# solar_datalogger_workshop.net
KiCad netlist of a schematic drawn in EAGLE
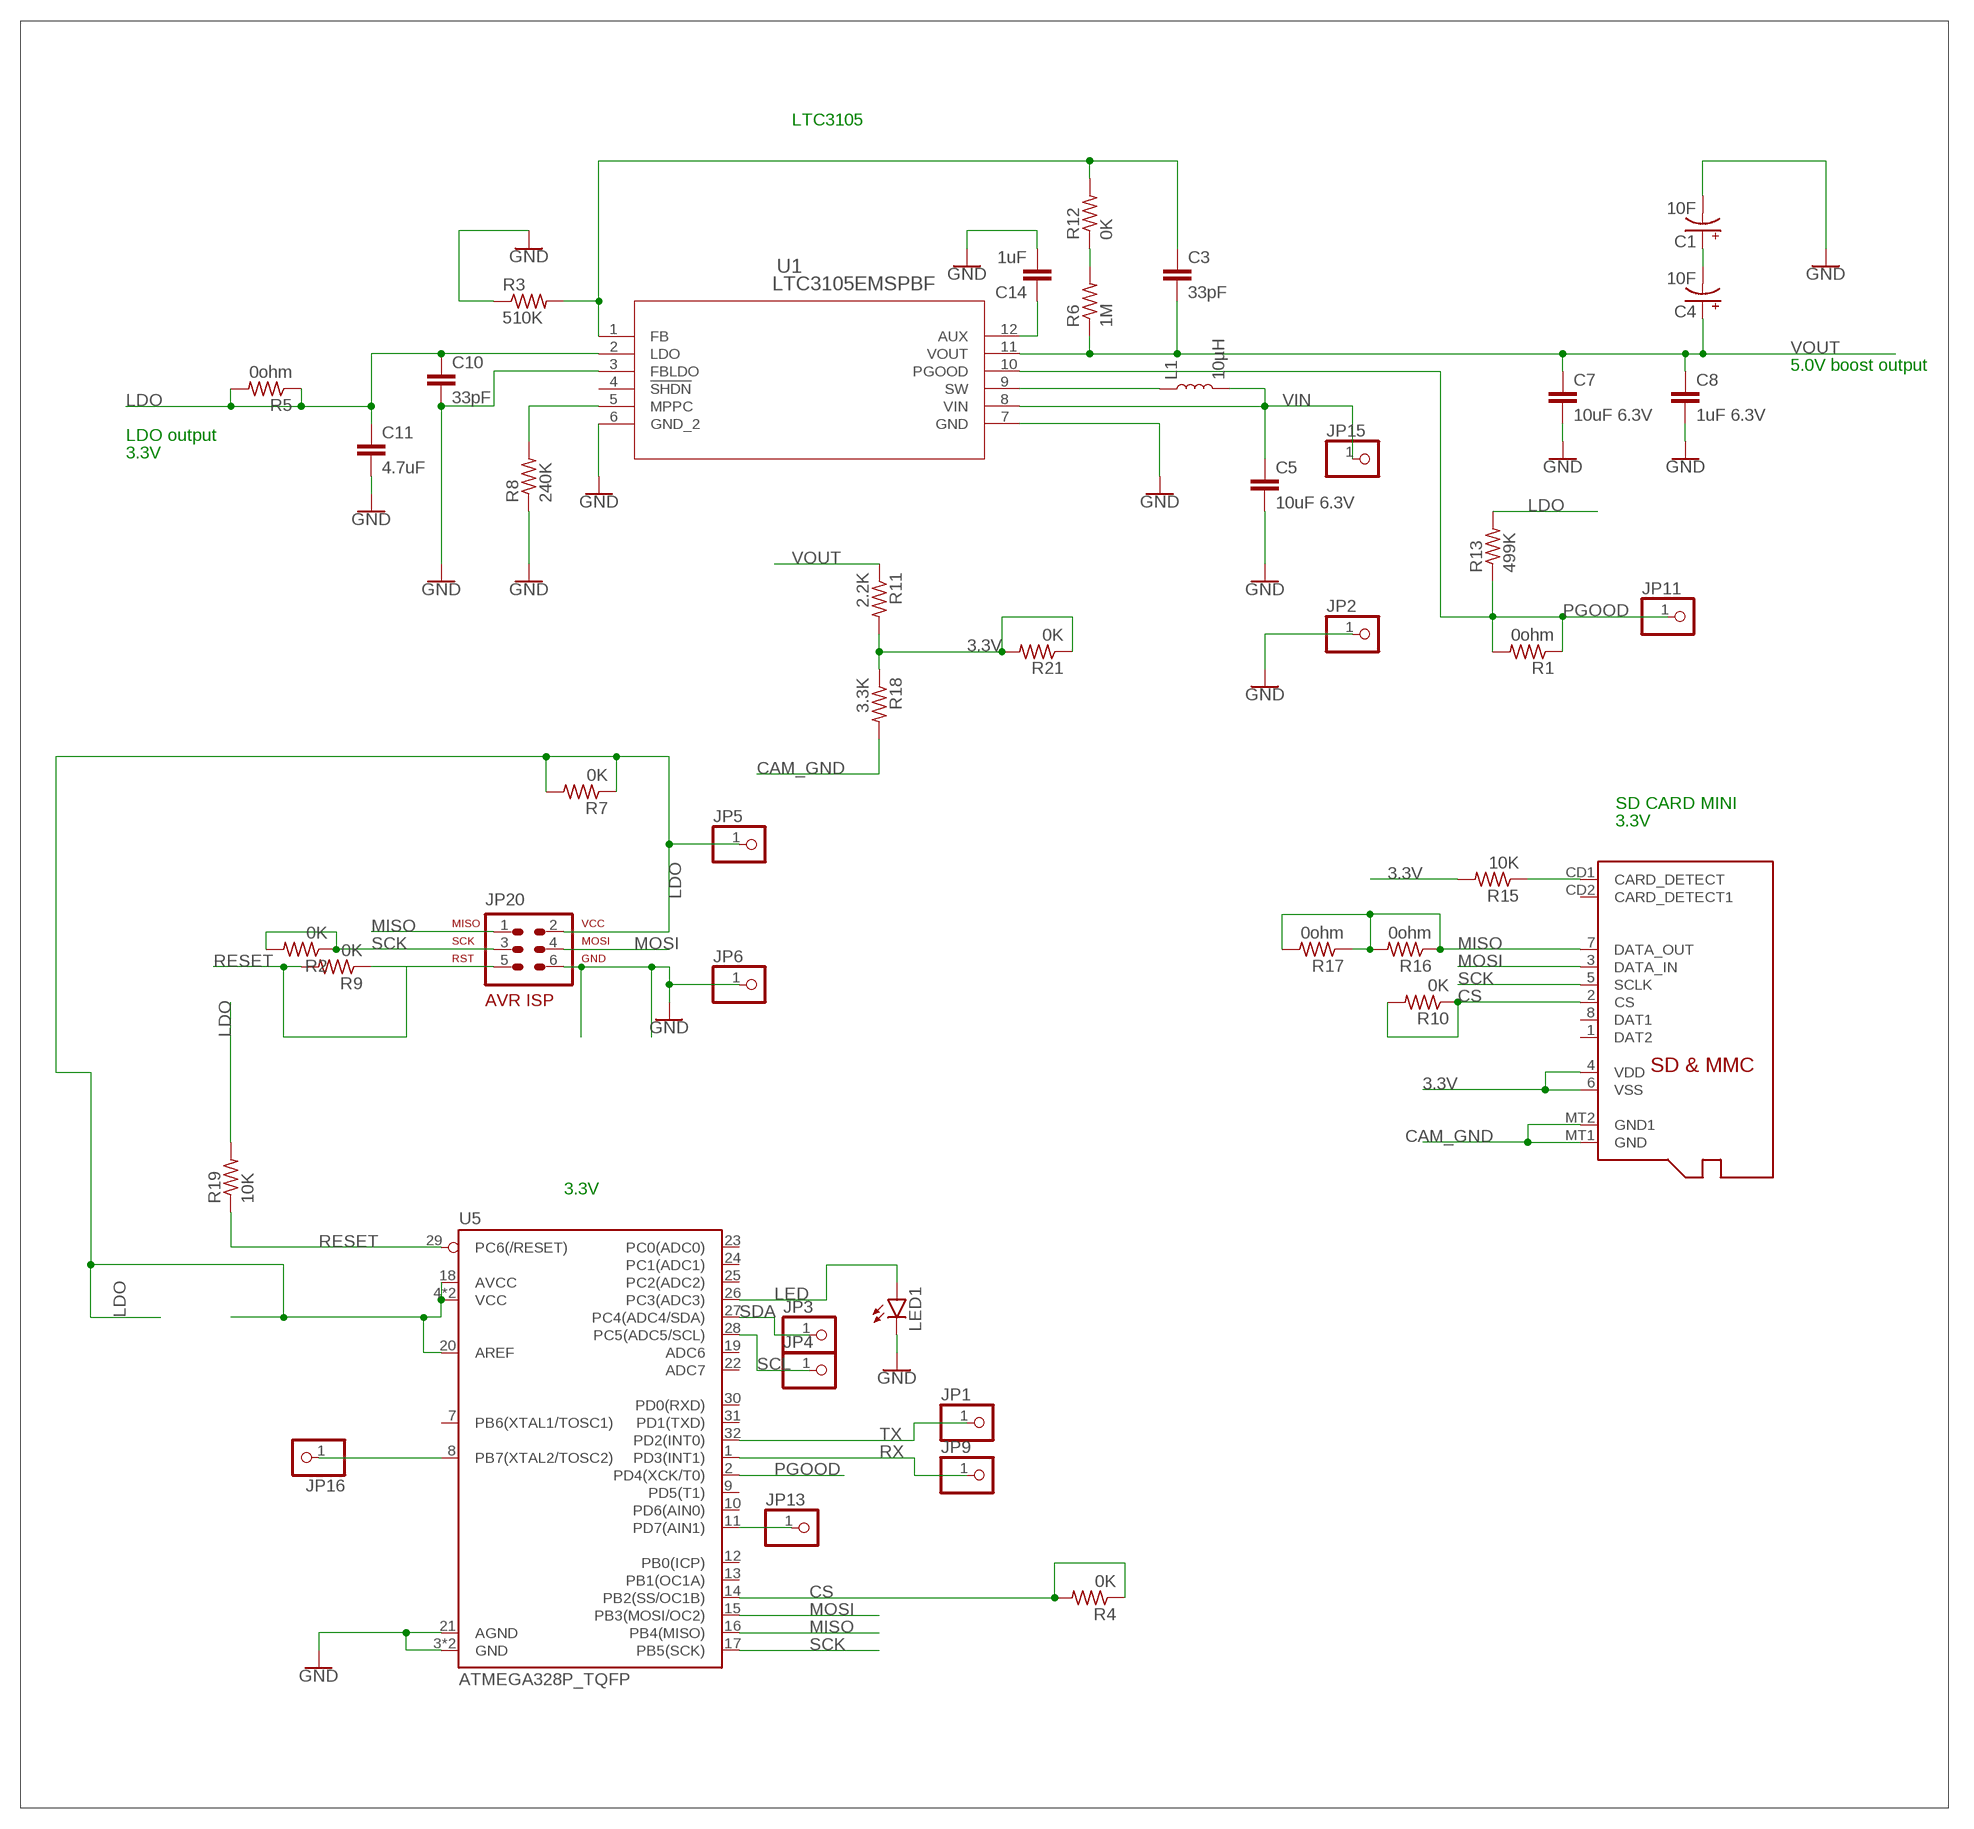
[diagram p0: schematic, sheet 1]

(export (version "E")
  (design (tool "Eeschema 10.0.6"))
  (components
    (comp (ref "C1")
      (value "10F")
      (footprint "eagle-import:CAP-RADIAL-5MM-21.5MM")
      (libsource (lib "eagle-import") (part "1F-EDLC"))
    )
    (comp (ref "C3")
      (value "33pF")
      (footprint "eagle-import:1206")
      (libsource (lib "eagle-import") (part "2.2UF-1206-50V-10%"))
    )
    (comp (ref "C4")
      (value "10F")
      (footprint "eagle-import:CAP-RADIAL-5MM-21.5MM")
      (libsource (lib "eagle-import") (part "1F-EDLC"))
    )
    (comp (ref "C5")
      (value "10uF 6.3V")
      (footprint "eagle-import:1206")
      (libsource (lib "eagle-import") (part "2.2UF-1206-50V-10%"))
    )
    (comp (ref "C7")
      (value "10uF 6.3V")
      (footprint "eagle-import:1206")
      (libsource (lib "eagle-import") (part "2.2UF-1206-50V-10%"))
    )
    (comp (ref "C8")
      (value "1uF 6.3V")
      (footprint "eagle-import:1206")
      (libsource (lib "eagle-import") (part "2.2UF-1206-50V-10%"))
    )
    (comp (ref "C10")
      (value "33pF")
      (footprint "eagle-import:1206")
      (libsource (lib "eagle-import") (part "2.2UF-1206-50V-10%"))
    )
    (comp (ref "C11")
      (value "4.7uF")
      (footprint "eagle-import:1206")
      (libsource (lib "eagle-import") (part "2.2UF-1206-50V-10%"))
    )
    (comp (ref "C14")
      (value "1uF")
      (footprint "eagle-import:1206")
      (libsource (lib "eagle-import") (part "2.2UF-1206-50V-10%"))
    )
    (comp (ref "JP1")
      (value "PINHD-1X1CB")
      (footprint "eagle-import:1X01-CLEANBIG")
      (libsource (lib "eagle-import") (part "PINHD-1X1CB"))
    )
    (comp (ref "JP2")
      (value "PINHD-1X1CB")
      (footprint "eagle-import:1X01-CLEANBIG")
      (libsource (lib "eagle-import") (part "PINHD-1X1CB"))
    )
    (comp (ref "JP3")
      (value "PINHD-1X1CB")
      (footprint "eagle-import:1X01-CLEANBIG")
      (libsource (lib "eagle-import") (part "PINHD-1X1CB"))
    )
    (comp (ref "JP4")
      (value "PINHD-1X1CB")
      (footprint "eagle-import:1X01-CLEANBIG")
      (libsource (lib "eagle-import") (part "PINHD-1X1CB"))
    )
    (comp (ref "JP5")
      (value "PINHD-1X1CB")
      (footprint "eagle-import:1X01-CLEANBIG")
      (libsource (lib "eagle-import") (part "PINHD-1X1CB"))
    )
    (comp (ref "JP6")
      (value "PINHD-1X1CB")
      (footprint "eagle-import:1X01-CLEANBIG")
      (libsource (lib "eagle-import") (part "PINHD-1X1CB"))
    )
    (comp (ref "JP9")
      (value "PINHD-1X1CB")
      (footprint "eagle-import:1X01-CLEANBIG")
      (libsource (lib "eagle-import") (part "PINHD-1X1CB"))
    )
    (comp (ref "JP11")
      (value "PINHD-1X1CB")
      (footprint "eagle-import:1X01-CLEANBIG")
      (libsource (lib "eagle-import") (part "PINHD-1X1CB"))
    )
    (comp (ref "JP13")
      (value "PINHD-1X1CB")
      (footprint "eagle-import:1X01-CLEANBIG")
      (libsource (lib "eagle-import") (part "PINHD-1X1CB"))
    )
    (comp (ref "JP15")
      (value "PINHD-1X1CB")
      (footprint "eagle-import:1X01-CLEANBIG")
      (libsource (lib "eagle-import") (part "PINHD-1X1CB"))
    )
    (comp (ref "JP16")
      (value "PINHD-1X1CB")
      (footprint "eagle-import:1X01-CLEANBIG")
      (libsource (lib "eagle-import") (part "PINHD-1X1CB"))
    )
    (comp (ref "JP20")
      (value "AVR-ISP-6HORZ")
      (footprint "eagle-import:AVR-ISP-6R")
      (libsource (lib "eagle-import") (part "AVR-ISP-6HORZ"))
    )
    (comp (ref "L1")
      (value "10µH")
      (footprint "eagle-import:INDUCTOR_2.2UH")
      (libsource (lib "eagle-import") (part "INDUCTOR-VLF4012AT-2.2UH"))
    )
    (comp (ref "LED1")
      (value "LEDSML1206")
      (footprint "eagle-import:SML1206")
      (libsource (lib "eagle-import") (part "LEDSML1206"))
    )
    (comp (ref "R1")
      (value "0ohm")
      (footprint "eagle-import:R1206")
      (libsource (lib "eagle-import") (part "R-US_R1206"))
    )
    (comp (ref "R2")
      (value "0K")
      (footprint "eagle-import:R1206")
      (libsource (lib "eagle-import") (part "R-US_R1206"))
    )
    (comp (ref "R3")
      (value "510K")
      (footprint "eagle-import:R1206")
      (libsource (lib "eagle-import") (part "R-US_R1206"))
    )
    (comp (ref "R4")
      (value "0K")
      (footprint "eagle-import:R1206")
      (libsource (lib "eagle-import") (part "R-US_R1206"))
    )
    (comp (ref "R5")
      (value "0ohm")
      (footprint "eagle-import:R1206")
      (libsource (lib "eagle-import") (part "R-US_R1206"))
    )
    (comp (ref "R6")
      (value "1M")
      (footprint "eagle-import:R1206")
      (libsource (lib "eagle-import") (part "R-US_R1206"))
    )
    (comp (ref "R7")
      (value "0K")
      (footprint "eagle-import:R1206")
      (libsource (lib "eagle-import") (part "R-US_R1206"))
    )
    (comp (ref "R8")
      (value "240K")
      (footprint "eagle-import:R1206")
      (libsource (lib "eagle-import") (part "R-US_R1206"))
    )
    (comp (ref "R9")
      (value "0K")
      (footprint "eagle-import:R1206")
      (libsource (lib "eagle-import") (part "R-US_R1206"))
    )
    (comp (ref "R10")
      (value "0K")
      (footprint "eagle-import:R1206")
      (libsource (lib "eagle-import") (part "R-US_R1206"))
    )
    (comp (ref "R11")
      (value "2.2K")
      (footprint "eagle-import:R1206")
      (libsource (lib "eagle-import") (part "R-US_R1206"))
    )
    (comp (ref "R12")
      (value "0K")
      (footprint "eagle-import:R1206")
      (libsource (lib "eagle-import") (part "R-US_R1206"))
    )
    (comp (ref "R13")
      (value "499K")
      (footprint "eagle-import:R1206")
      (libsource (lib "eagle-import") (part "R-US_R1206"))
    )
    (comp (ref "R15")
      (value "10K")
      (footprint "eagle-import:R1206")
      (libsource (lib "eagle-import") (part "R-US_R1206"))
    )
    (comp (ref "R16")
      (value "0ohm")
      (footprint "eagle-import:R1206")
      (libsource (lib "eagle-import") (part "R-US_R1206"))
    )
    (comp (ref "R17")
      (value "0ohm")
      (footprint "eagle-import:R1206")
      (libsource (lib "eagle-import") (part "R-US_R1206"))
    )
    (comp (ref "R18")
      (value "3.3K")
      (footprint "eagle-import:R1206")
      (libsource (lib "eagle-import") (part "R-US_R1206"))
    )
    (comp (ref "R19")
      (value "10K")
      (footprint "eagle-import:R1206")
      (libsource (lib "eagle-import") (part "R-US_R1206"))
    )
    (comp (ref "R21")
      (value "0K")
      (footprint "eagle-import:R1206")
      (libsource (lib "eagle-import") (part "R-US_R1206"))
    )
    (comp (ref "U$1")
      (value "MICROSD")
      (footprint "eagle-import:MICROSD")
      (libsource (lib "eagle-import") (part "MICROSD"))
    )
    (comp (ref "U1")
      (value "LTC3105EMSPBF")
      (footprint "eagle-import:MSOP-12_MS")
      (fields (field (name "MANUFACTURER_PART_NUMBER") "ltc3105ems#pbf"))
      (libsource (lib "eagle-import") (part "LTC3105EMSPBF"))
    )
    (comp (ref "U5")
      (value "ATMEGA328P_TQFP")
      (footprint "eagle-import:TQFP32-08")
      (libsource (lib "eagle-import") (part "ATMEGA328P_TQFP"))
    )
  )
  (nets
    (net (code "1") (name "/3.3V") (class "Default")
      (node (ref "R11") (pin "2") (pinfunction "2_2") (pintype "passive"))
      (node (ref "R15") (pin "2") (pinfunction "2_2") (pintype "passive"))
      (node (ref "R18") (pin "1") (pinfunction "1_1") (pintype "passive"))
      (node (ref "R21") (pin "1") (pinfunction "1_1") (pintype "passive"))
      (node (ref "R21") (pin "2") (pinfunction "2_2") (pintype "passive"))
      (node (ref "U$1") (pin "4") (pinfunction "VDD_4") (pintype "power_in"))
      (node (ref "U$1") (pin "6") (pinfunction "VSS_6") (pintype "power_in"))
    )
    (net (code "2") (name "/CAM_GND") (class "Default")
      (node (ref "R18") (pin "2") (pinfunction "2_2") (pintype "passive"))
      (node (ref "U$1") (pin "MT1") (pinfunction "GND_MT1") (pintype "power_in"))
      (node (ref "U$1") (pin "MT2") (pinfunction "GND1_MT2") (pintype "power_in"))
    )
    (net (code "3") (name "/CS") (class "Default")
      (node (ref "R10") (pin "1") (pinfunction "1_1") (pintype "passive"))
      (node (ref "R10") (pin "2") (pinfunction "2_2") (pintype "passive"))
      (node (ref "R4") (pin "1") (pinfunction "1_1") (pintype "passive"))
      (node (ref "R4") (pin "2") (pinfunction "2_2") (pintype "passive"))
      (node (ref "U$1") (pin "2") (pinfunction "CS_2") (pintype "input"))
      (node (ref "U5") (pin "14") (pinfunction "PB2(SS/OC1B)_14") (pintype "bidirectional"))
    )
    (net (code "4") (name "/LDO") (class "Default")
      (node (ref "C10") (pin "1") (pinfunction "1_1") (pintype "passive"))
      (node (ref "C11") (pin "1") (pinfunction "1_1") (pintype "passive"))
      (node (ref "JP20") (pin "2") (pinfunction "2_2") (pintype "passive"))
      (node (ref "JP5") (pin "1") (pinfunction "1_1") (pintype "passive"))
      (node (ref "R13") (pin "2") (pinfunction "2_2") (pintype "passive"))
      (node (ref "R19") (pin "2") (pinfunction "2_2") (pintype "passive"))
      (node (ref "R5") (pin "1") (pinfunction "1_1") (pintype "passive"))
      (node (ref "R5") (pin "2") (pinfunction "2_2") (pintype "passive"))
      (node (ref "R7") (pin "1") (pinfunction "1_1") (pintype "passive"))
      (node (ref "R7") (pin "2") (pinfunction "2_2") (pintype "passive"))
      (node (ref "U1") (pin "2") (pinfunction "LDO_2") (pintype "passive"))
      (node (ref "U5") (pin "18") (pinfunction "AVCC_18") (pintype "bidirectional"))
      (node (ref "U5") (pin "20") (pinfunction "AREF_20") (pintype "bidirectional"))
      (node (ref "U5") (pin "4") (pinfunction "VCC_4") (pintype "bidirectional"))
      (node (ref "U5") (pin "6") (pinfunction "VCC_6") (pintype "bidirectional"))
    )
    (net (code "5") (name "/LED") (class "Default")
      (node (ref "LED1") (pin "A") (pinfunction "A_A") (pintype "passive"))
      (node (ref "U5") (pin "26") (pinfunction "PC3(ADC3)_26") (pintype "bidirectional"))
    )
    (net (code "6") (name "/MISO") (class "Default")
      (node (ref "JP20") (pin "1") (pinfunction "1_1") (pintype "passive"))
      (node (ref "R16") (pin "1") (pinfunction "1_1") (pintype "passive"))
      (node (ref "R16") (pin "2") (pinfunction "2_2") (pintype "passive"))
      (node (ref "R17") (pin "1") (pinfunction "1_1") (pintype "passive"))
      (node (ref "R17") (pin "2") (pinfunction "2_2") (pintype "passive"))
      (node (ref "U$1") (pin "7") (pinfunction "DATA_OUT_7") (pintype "output"))
      (node (ref "U5") (pin "16") (pinfunction "PB4(MISO)_16") (pintype "bidirectional"))
    )
    (net (code "7") (name "/MOSI") (class "Default")
      (node (ref "JP20") (pin "4") (pinfunction "4_4") (pintype "passive"))
      (node (ref "U$1") (pin "3") (pinfunction "DATA_IN_3") (pintype "input"))
      (node (ref "U5") (pin "15") (pinfunction "PB3(MOSI/OC2)_15") (pintype "bidirectional"))
    )
    (net (code "8") (name "/PGOOD") (class "Default")
      (node (ref "JP11") (pin "1") (pinfunction "1_1") (pintype "passive"))
      (node (ref "R1") (pin "1") (pinfunction "1_1") (pintype "passive"))
      (node (ref "R1") (pin "2") (pinfunction "2_2") (pintype "passive"))
      (node (ref "R13") (pin "1") (pinfunction "1_1") (pintype "passive"))
      (node (ref "U1") (pin "10") (pinfunction "PGOOD_10") (pintype "passive"))
      (node (ref "U5") (pin "2") (pinfunction "PD4(XCK/T0)_2") (pintype "bidirectional"))
    )
    (net (code "9") (name "/RESET") (class "Default")
      (node (ref "JP20") (pin "5") (pinfunction "5_5") (pintype "passive"))
      (node (ref "R19") (pin "1") (pinfunction "1_1") (pintype "passive"))
      (node (ref "R9") (pin "1") (pinfunction "1_1") (pintype "passive"))
      (node (ref "R9") (pin "2") (pinfunction "2_2") (pintype "passive"))
      (node (ref "U5") (pin "29") (pinfunction "PC6(/RESET)_29") (pintype "bidirectional"))
    )
    (net (code "10") (name "/RX") (class "Default")
      (node (ref "JP9") (pin "1") (pinfunction "1_1") (pintype "passive"))
      (node (ref "U5") (pin "1") (pinfunction "PD3(INT1)_1") (pintype "bidirectional"))
    )
    (net (code "11") (name "/SCK") (class "Default")
      (node (ref "JP20") (pin "3") (pinfunction "3_3") (pintype "passive"))
      (node (ref "R2") (pin "1") (pinfunction "1_1") (pintype "passive"))
      (node (ref "R2") (pin "2") (pinfunction "2_2") (pintype "passive"))
      (node (ref "U$1") (pin "5") (pinfunction "SCLK_5") (pintype "input"))
      (node (ref "U5") (pin "17") (pinfunction "PB5(SCK)_17") (pintype "bidirectional"))
    )
    (net (code "12") (name "/SCL") (class "Default")
      (node (ref "JP4") (pin "1") (pinfunction "1_1") (pintype "passive"))
      (node (ref "U5") (pin "28") (pinfunction "PC5(ADC5/SCL)_28") (pintype "bidirectional"))
    )
    (net (code "13") (name "/SDA") (class "Default")
      (node (ref "JP3") (pin "1") (pinfunction "1_1") (pintype "passive"))
      (node (ref "U5") (pin "27") (pinfunction "PC4(ADC4/SDA)_27") (pintype "bidirectional"))
    )
    (net (code "14") (name "/TX") (class "Default")
      (node (ref "JP1") (pin "1") (pinfunction "1_1") (pintype "passive"))
      (node (ref "U5") (pin "32") (pinfunction "PD2(INT0)_32") (pintype "bidirectional"))
    )
    (net (code "15") (name "/VIN") (class "Default")
      (node (ref "C5") (pin "1") (pinfunction "1_1") (pintype "passive"))
      (node (ref "JP15") (pin "1") (pinfunction "1_1") (pintype "passive"))
      (node (ref "L1") (pin "P$2") (pinfunction "2_P$2") (pintype "passive"))
      (node (ref "U1") (pin "8") (pinfunction "VIN_8") (pintype "input"))
    )
    (net (code "16") (name "/VOUT") (class "Default")
      (node (ref "C3") (pin "2") (pinfunction "2_2") (pintype "passive"))
      (node (ref "C4") (pin "+") (pinfunction "+_+") (pintype "passive"))
      (node (ref "C7") (pin "1") (pinfunction "1_1") (pintype "passive"))
      (node (ref "C8") (pin "1") (pinfunction "1_1") (pintype "passive"))
      (node (ref "R11") (pin "1") (pinfunction "1_1") (pintype "passive"))
      (node (ref "R6") (pin "1") (pinfunction "1_1") (pintype "passive"))
      (node (ref "U1") (pin "11") (pinfunction "VOUT_11") (pintype "passive"))
    )
    (net (code "17") (name "GND") (class "Default")
      (node (ref "C1") (pin "-") (pinfunction "-_-") (pintype "passive"))
      (node (ref "C10") (pin "2") (pinfunction "2_2") (pintype "passive"))
      (node (ref "C11") (pin "2") (pinfunction "2_2") (pintype "passive"))
      (node (ref "C14") (pin "2") (pinfunction "2_2") (pintype "passive"))
      (node (ref "C5") (pin "2") (pinfunction "2_2") (pintype "passive"))
      (node (ref "C7") (pin "2") (pinfunction "2_2") (pintype "passive"))
      (node (ref "C8") (pin "2") (pinfunction "2_2") (pintype "passive"))
      (node (ref "JP2") (pin "1") (pinfunction "1_1") (pintype "passive"))
      (node (ref "JP20") (pin "6") (pinfunction "6_6") (pintype "passive"))
      (node (ref "JP6") (pin "1") (pinfunction "1_1") (pintype "passive"))
      (node (ref "LED1") (pin "C") (pinfunction "C_C") (pintype "passive"))
      (node (ref "R3") (pin "1") (pinfunction "1_1") (pintype "passive"))
      (node (ref "R8") (pin "1") (pinfunction "1_1") (pintype "passive"))
      (node (ref "U1") (pin "3") (pinfunction "FBLDO_3") (pintype "bidirectional"))
      (node (ref "U1") (pin "6") (pinfunction "GND_2_6") (pintype "power_in"))
      (node (ref "U1") (pin "7") (pinfunction "GND_7") (pintype "power_in"))
      (node (ref "U5") (pin "21") (pinfunction "AGND_21") (pintype "bidirectional"))
      (node (ref "U5") (pin "3") (pinfunction "GND_3") (pintype "bidirectional"))
      (node (ref "U5") (pin "5") (pinfunction "GND_5") (pintype "bidirectional"))
    )
    (net (code "18") (name "Net-(C1-Pad+)") (class "Default")
      (node (ref "C1") (pin "+") (pinfunction "+_+") (pintype "passive"))
      (node (ref "C4") (pin "-") (pinfunction "-_-") (pintype "passive"))
    )
    (net (code "19") (name "Net-(L1-1)") (class "Default")
      (node (ref "L1") (pin "P$1") (pinfunction "1_P$1") (pintype "passive"))
      (node (ref "U1") (pin "9") (pinfunction "SW_9") (pintype "passive"))
    )
    (net (code "20") (name "Net-(R12-Pad1)") (class "Default")
      (node (ref "R12") (pin "1") (pinfunction "1_1") (pintype "passive"))
      (node (ref "R6") (pin "2") (pinfunction "2_2") (pintype "passive"))
    )
    (net (code "21") (name "Net-(U$1-CARD_DETECT)") (class "Default")
      (node (ref "R15") (pin "1") (pinfunction "1_1") (pintype "passive"))
      (node (ref "U$1") (pin "CD1") (pinfunction "CARD_DETECT_CD1") (pintype "passive"))
    )
    (net (code "22") (name "Net-(U1-AUX)") (class "Default")
      (node (ref "C14") (pin "1") (pinfunction "1_1") (pintype "passive"))
      (node (ref "U1") (pin "12") (pinfunction "AUX_12") (pintype "passive"))
    )
    (net (code "23") (name "Net-(U1-FB)") (class "Default")
      (node (ref "C3") (pin "1") (pinfunction "1_1") (pintype "passive"))
      (node (ref "R12") (pin "2") (pinfunction "2_2") (pintype "passive"))
      (node (ref "R3") (pin "2") (pinfunction "2_2") (pintype "passive"))
      (node (ref "U1") (pin "1") (pinfunction "FB_1") (pintype "bidirectional"))
    )
    (net (code "24") (name "Net-(U1-MPPC)") (class "Default")
      (node (ref "R8") (pin "2") (pinfunction "2_2") (pintype "passive"))
      (node (ref "U1") (pin "5") (pinfunction "MPPC_5") (pintype "input"))
    )
    (net (code "25") (name "Net-(U5-PB7(XTAL2{slash}TOSC2))") (class "Default")
      (node (ref "JP16") (pin "1") (pinfunction "1_1") (pintype "passive"))
      (node (ref "U5") (pin "8") (pinfunction "PB7(XTAL2/TOSC2)_8") (pintype "bidirectional"))
    )
    (net (code "26") (name "Net-(U5-PD7(AIN1))") (class "Default")
      (node (ref "JP13") (pin "1") (pinfunction "1_1") (pintype "passive"))
      (node (ref "U5") (pin "11") (pinfunction "PD7(AIN1)_11") (pintype "bidirectional"))
    )
    (net (code "27") (name "unconnected-(U$1-CARD_DETECT1-PadCD2)") (class "Default")
      (node (ref "U$1") (pin "CD2") (pinfunction "CARD_DETECT1_CD2") (pintype "passive"))
    )
    (net (code "28") (name "unconnected-(U$1-DAT1-Pad8)") (class "Default")
      (node (ref "U$1") (pin "8") (pinfunction "DAT1_8") (pintype "bidirectional"))
    )
    (net (code "29") (name "unconnected-(U$1-DAT2-Pad1)") (class "Default")
      (node (ref "U$1") (pin "1") (pinfunction "DAT2_1") (pintype "bidirectional"))
    )
    (net (code "30") (name "unconnected-(U1-~{SHDN}-Pad4)") (class "Default")
      (node (ref "U1") (pin "4") (pinfunction "~{SHDN}_4") (pintype "input"))
    )
    (net (code "31") (name "unconnected-(U5-ADC6-Pad19)") (class "Default")
      (node (ref "U5") (pin "19") (pinfunction "ADC6_19") (pintype "bidirectional"))
    )
    (net (code "32") (name "unconnected-(U5-ADC7-Pad22)") (class "Default")
      (node (ref "U5") (pin "22") (pinfunction "ADC7_22") (pintype "bidirectional"))
    )
    (net (code "33") (name "unconnected-(U5-PB0(ICP)-Pad12)") (class "Default")
      (node (ref "U5") (pin "12") (pinfunction "PB0(ICP)_12") (pintype "bidirectional"))
    )
    (net (code "34") (name "unconnected-(U5-PB1(OC1A)-Pad13)") (class "Default")
      (node (ref "U5") (pin "13") (pinfunction "PB1(OC1A)_13") (pintype "bidirectional"))
    )
    (net (code "35") (name "unconnected-(U5-PB6(XTAL1{slash}TOSC1)-Pad7)") (class "Default")
      (node (ref "U5") (pin "7") (pinfunction "PB6(XTAL1/TOSC1)_7") (pintype "bidirectional"))
    )
    (net (code "36") (name "unconnected-(U5-PC0(ADC0)-Pad23)") (class "Default")
      (node (ref "U5") (pin "23") (pinfunction "PC0(ADC0)_23") (pintype "bidirectional"))
    )
    (net (code "37") (name "unconnected-(U5-PC1(ADC1)-Pad24)") (class "Default")
      (node (ref "U5") (pin "24") (pinfunction "PC1(ADC1)_24") (pintype "bidirectional"))
    )
    (net (code "38") (name "unconnected-(U5-PC2(ADC2)-Pad25)") (class "Default")
      (node (ref "U5") (pin "25") (pinfunction "PC2(ADC2)_25") (pintype "bidirectional"))
    )
    (net (code "39") (name "unconnected-(U5-PD0(RXD)-Pad30)") (class "Default")
      (node (ref "U5") (pin "30") (pinfunction "PD0(RXD)_30") (pintype "bidirectional"))
    )
    (net (code "40") (name "unconnected-(U5-PD1(TXD)-Pad31)") (class "Default")
      (node (ref "U5") (pin "31") (pinfunction "PD1(TXD)_31") (pintype "bidirectional"))
    )
    (net (code "41") (name "unconnected-(U5-PD5(T1)-Pad9)") (class "Default")
      (node (ref "U5") (pin "9") (pinfunction "PD5(T1)_9") (pintype "bidirectional"))
    )
    (net (code "42") (name "unconnected-(U5-PD6(AIN0)-Pad10)") (class "Default")
      (node (ref "U5") (pin "10") (pinfunction "PD6(AIN0)_10") (pintype "bidirectional"))
    )
  )
)
